# Vile_Boon.net
KiCad netlist of a schematic drawn in EAGLE
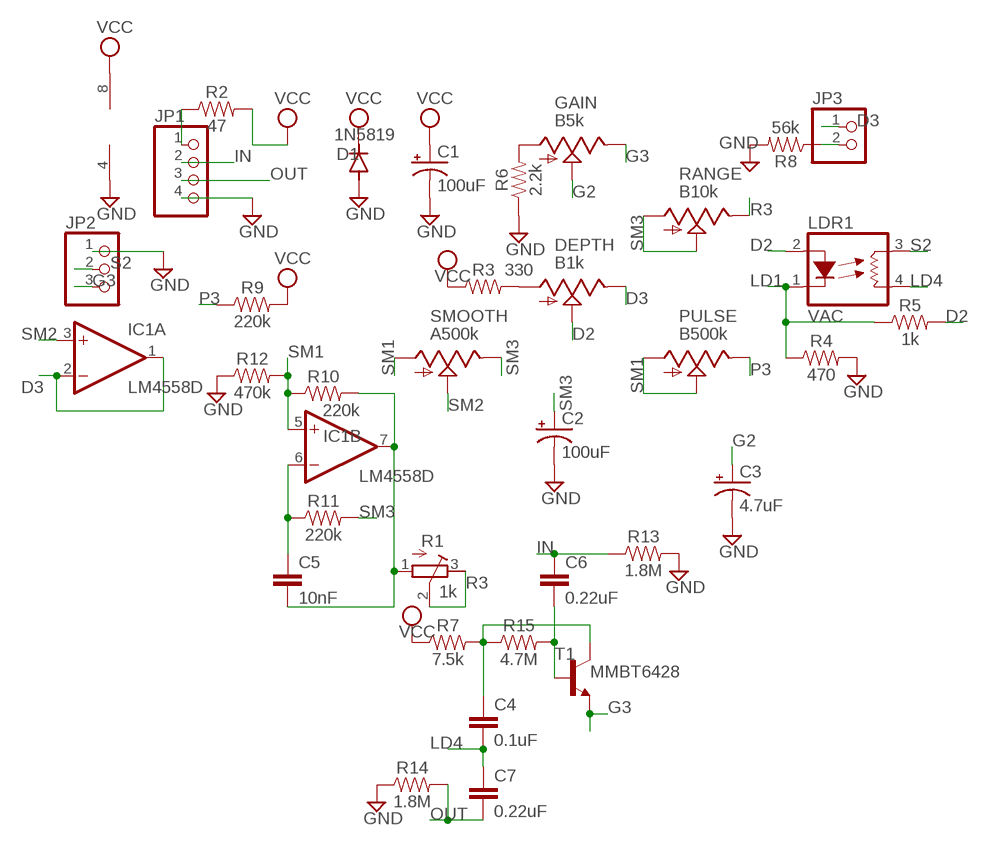
[diagram p0: schematic, sheet 1]

(export (version "E")
  (design (tool "Eeschema 10.0.6"))
  (components
    (comp (ref "C1")
      (value "100uF")
      (footprint "eagle-import:PAN_B_SMD+THRU")
      (libsource (lib "eagle-import") (part "CAP_SMD+THRUPAN_B"))
    )
    (comp (ref "C2")
      (value "100uF")
      (footprint "eagle-import:PAN_B_SMD+THRU")
      (libsource (lib "eagle-import") (part "CAP_SMD+THRUPAN_B"))
    )
    (comp (ref "C3")
      (value "4.7uF")
      (footprint "eagle-import:PAN_B_SMD+THRU")
      (libsource (lib "eagle-import") (part "CAP_SMD+THRUPAN_B"))
    )
    (comp (ref "C4")
      (value "0.1uF")
      (footprint "eagle-import:0603")
      (libsource (lib "eagle-import") (part "0.1UF-0603-25V-(+80/-20%)"))
    )
    (comp (ref "C5")
      (value "10nF")
      (footprint "eagle-import:0603")
      (libsource (lib "eagle-import") (part "10NF-0603-50V-10%"))
    )
    (comp (ref "C6")
      (value "0.22uF")
      (footprint "eagle-import:0603")
      (libsource (lib "eagle-import") (part "0.22UF-0603-25V-10%"))
    )
    (comp (ref "C7")
      (value "0.22uF")
      (footprint "eagle-import:0603")
      (libsource (lib "eagle-import") (part "0.22UF-0603-25V-10%"))
    )
    (comp (ref "D1")
      (value "1N5819")
      (footprint "eagle-import:SOD123")
      (libsource (lib "eagle-import") (part "DIODE-SOD123"))
    )
    (comp (ref "DEPTH")
      (value "B1k")
      (footprint "eagle-import:9MM_SNAP-IN_POT")
      (libsource (lib "eagle-import") (part "9MM_SNAP-IN_POT_"))
    )
    (comp (ref "GAIN")
      (value "B5k")
      (footprint "eagle-import:9MM_SNAP-IN_POT")
      (libsource (lib "eagle-import") (part "9MM_SNAP-IN_POT_"))
    )
    (comp (ref "IC1")
      (value "LM4558D")
      (footprint "eagle-import:SO08")
      (libsource (lib "eagle-import") (part "4558DLM"))
    )
    (comp (ref "JP1")
      (value "PINHD-1X4")
      (footprint "eagle-import:1X04")
      (libsource (lib "eagle-import") (part "PINHD-1X4"))
    )
    (comp (ref "JP2")
      (value "PINHD-1X3")
      (footprint "eagle-import:1X03")
      (libsource (lib "eagle-import") (part "PINHD-1X3"))
    )
    (comp (ref "JP3")
      (value "PINHD-1X2")
      (footprint "eagle-import:1X02")
      (libsource (lib "eagle-import") (part "PINHD-1X2"))
    )
    (comp (ref "LDR1")
      (value "VAC")
      (footprint "eagle-import:VACTROL_4PIN_VTL5C")
      (libsource (lib "eagle-import") (part "VACTROL_4PIN"))
    )
    (comp (ref "PULSE")
      (value "B500k")
      (footprint "eagle-import:9MM_SNAP-IN_POT")
      (libsource (lib "eagle-import") (part "9MM_SNAP-IN_POT_"))
    )
    (comp (ref "R1")
      (value "1k")
      (footprint "eagle-import:RTRIM3296W")
      (libsource (lib "eagle-import") (part "R-TRIMM3296W"))
    )
    (comp (ref "R2")
      (value "47")
      (footprint "eagle-import:0603")
      (libsource (lib "eagle-import") (part "47KOHM-0603-1/10W-1%"))
    )
    (comp (ref "R3")
      (value "330")
      (footprint "eagle-import:0603")
      (libsource (lib "eagle-import") (part "47KOHM-0603-1/10W-1%"))
    )
    (comp (ref "R4")
      (value "470")
      (footprint "eagle-import:0603")
      (libsource (lib "eagle-import") (part "47KOHM-0603-1/10W-1%"))
    )
    (comp (ref "R5")
      (value "1k")
      (footprint "eagle-import:0603")
      (libsource (lib "eagle-import") (part "1KOHM-0603-1/10W-1%"))
    )
    (comp (ref "R6")
      (value "2.2k")
      (footprint "eagle-import:0603")
      (libsource (lib "eagle-import") (part "2.2KOHM-0603-1/10W-1%"))
    )
    (comp (ref "R7")
      (value "7.5k")
      (footprint "eagle-import:0603")
      (libsource (lib "eagle-import") (part "6.8KOHM-0603-1/10W-1%"))
    )
    (comp (ref "R8")
      (value "56k")
      (footprint "eagle-import:0603")
      (libsource (lib "eagle-import") (part "47KOHM-0603-1/10W-1%"))
    )
    (comp (ref "R9")
      (value "220k")
      (footprint "eagle-import:0603")
      (libsource (lib "eagle-import") (part "220KOHM-0603-1/10W-1%"))
    )
    (comp (ref "R10")
      (value "220k")
      (footprint "eagle-import:0603")
      (libsource (lib "eagle-import") (part "220KOHM-0603-1/10W-1%"))
    )
    (comp (ref "R11")
      (value "220k")
      (footprint "eagle-import:0603")
      (libsource (lib "eagle-import") (part "220KOHM-0603-1/10W-1%"))
    )
    (comp (ref "R12")
      (value "470k")
      (footprint "eagle-import:0603")
      (libsource (lib "eagle-import") (part "470OHM-0603-1/10W-1%"))
    )
    (comp (ref "R13")
      (value "1.8M")
      (footprint "eagle-import:0603")
      (libsource (lib "eagle-import") (part "1MOHM-0603-1/4W-5%"))
    )
    (comp (ref "R14")
      (value "1.8M")
      (footprint "eagle-import:0603")
      (libsource (lib "eagle-import") (part "1MOHM-0603-1/4W-5%"))
    )
    (comp (ref "R15")
      (value "4.7M")
      (footprint "eagle-import:0603")
      (libsource (lib "eagle-import") (part "4.7KOHM-0603-1/10W-1%"))
    )
    (comp (ref "RANGE")
      (value "B10k")
      (footprint "eagle-import:9MM_SNAP-IN_POT")
      (libsource (lib "eagle-import") (part "9MM_SNAP-IN_POT_"))
    )
    (comp (ref "SMOOTH")
      (value "A500k")
      (footprint "eagle-import:9MM_SNAP-IN_POT")
      (libsource (lib "eagle-import") (part "9MM_SNAP-IN_POT_"))
    )
    (comp (ref "T1")
      (value "MMBT6428")
      (footprint "eagle-import:SOT23-BEC")
      (libsource (lib "eagle-import") (part "-NPN-SOT23-BECBFS17"))
    )
  )
  (nets
    (net (code "1") (name "/D2") (class "Default")
      (node (ref "DEPTH") (pin "2") (pinfunction "S_2") (pintype "passive"))
      (node (ref "LDR1") (pin "2") (pinfunction "LED+_2") (pintype "passive"))
      (node (ref "R5") (pin "2") (pinfunction "2_2") (pintype "passive"))
    )
    (net (code "2") (name "/D3") (class "Default")
      (node (ref "DEPTH") (pin "3") (pinfunction "E_3") (pintype "passive"))
      (node (ref "IC1") (pin "1") (pinfunction "OUT_1") (pintype "output"))
      (node (ref "IC1") (pin "2") (pinfunction "-IN_2") (pintype "input"))
      (node (ref "JP3") (pin "1") (pinfunction "1_1") (pintype "passive"))
    )
    (net (code "3") (name "/G2") (class "Default")
      (node (ref "C3") (pin "+") (pinfunction "+_+") (pintype "passive"))
      (node (ref "C3") (pin "++") (pinfunction "+_++") (pintype "passive"))
      (node (ref "GAIN") (pin "2") (pinfunction "S_2") (pintype "passive"))
    )
    (net (code "4") (name "/G3") (class "Default")
      (node (ref "GAIN") (pin "3") (pinfunction "E_3") (pintype "passive"))
      (node (ref "JP2") (pin "3") (pinfunction "3_3") (pintype "passive"))
      (node (ref "T1") (pin "E") (pinfunction "E_E") (pintype "passive"))
    )
    (net (code "5") (name "/IN") (class "Default")
      (node (ref "C6") (pin "1") (pinfunction "1_1") (pintype "passive"))
      (node (ref "JP1") (pin "2") (pinfunction "2_2") (pintype "passive"))
      (node (ref "R13") (pin "1") (pinfunction "1_1") (pintype "passive"))
    )
    (net (code "6") (name "/LD1") (class "Default")
      (node (ref "LDR1") (pin "1") (pinfunction "LED-_1") (pintype "passive"))
      (node (ref "R4") (pin "1") (pinfunction "1_1") (pintype "passive"))
      (node (ref "R5") (pin "1") (pinfunction "1_1") (pintype "passive"))
    )
    (net (code "7") (name "/LD4") (class "Default")
      (node (ref "C4") (pin "2") (pinfunction "2_2") (pintype "passive"))
      (node (ref "C7") (pin "1") (pinfunction "1_1") (pintype "passive"))
      (node (ref "LDR1") (pin "4") (pinfunction "RES2_4") (pintype "passive"))
    )
    (net (code "8") (name "/OUT") (class "Default")
      (node (ref "C7") (pin "2") (pinfunction "2_2") (pintype "passive"))
      (node (ref "JP1") (pin "3") (pinfunction "3_3") (pintype "passive"))
      (node (ref "R14") (pin "2") (pinfunction "2_2") (pintype "passive"))
    )
    (net (code "9") (name "/P3") (class "Default")
      (node (ref "PULSE") (pin "3") (pinfunction "E_3") (pintype "passive"))
      (node (ref "R9") (pin "1") (pinfunction "1_1") (pintype "passive"))
    )
    (net (code "10") (name "/R3") (class "Default")
      (node (ref "R1") (pin "2") (pinfunction "S_2") (pintype "passive"))
      (node (ref "R1") (pin "3") (pinfunction "E_3") (pintype "passive"))
      (node (ref "RANGE") (pin "3") (pinfunction "E_3") (pintype "passive"))
    )
    (net (code "11") (name "/S2") (class "Default")
      (node (ref "JP2") (pin "2") (pinfunction "2_2") (pintype "passive"))
      (node (ref "LDR1") (pin "3") (pinfunction "RES1_3") (pintype "passive"))
    )
    (net (code "12") (name "/SM1") (class "Default")
      (node (ref "IC1") (pin "5") (pinfunction "+IN_5") (pintype "input"))
      (node (ref "PULSE") (pin "1") (pinfunction "A_1") (pintype "passive"))
      (node (ref "PULSE") (pin "2") (pinfunction "S_2") (pintype "passive"))
      (node (ref "R10") (pin "1") (pinfunction "1_1") (pintype "passive"))
      (node (ref "R12") (pin "2") (pinfunction "2_2") (pintype "passive"))
      (node (ref "SMOOTH") (pin "1") (pinfunction "A_1") (pintype "passive"))
    )
    (net (code "13") (name "/SM2") (class "Default")
      (node (ref "IC1") (pin "3") (pinfunction "+IN_3") (pintype "input"))
      (node (ref "SMOOTH") (pin "2") (pinfunction "S_2") (pintype "passive"))
    )
    (net (code "14") (name "/SM3") (class "Default")
      (node (ref "C2") (pin "+") (pinfunction "+_+") (pintype "passive"))
      (node (ref "C2") (pin "++") (pinfunction "+_++") (pintype "passive"))
      (node (ref "R11") (pin "2") (pinfunction "2_2") (pintype "passive"))
      (node (ref "RANGE") (pin "1") (pinfunction "A_1") (pintype "passive"))
      (node (ref "RANGE") (pin "2") (pinfunction "S_2") (pintype "passive"))
      (node (ref "SMOOTH") (pin "3") (pinfunction "E_3") (pintype "passive"))
    )
    (net (code "15") (name "GND") (class "Default")
      (node (ref "C1") (pin "-") (pinfunction "-_-") (pintype "passive"))
      (node (ref "C1") (pin "--") (pinfunction "-_--") (pintype "passive"))
      (node (ref "C2") (pin "-") (pinfunction "-_-") (pintype "passive"))
      (node (ref "C2") (pin "--") (pinfunction "-_--") (pintype "passive"))
      (node (ref "C3") (pin "-") (pinfunction "-_-") (pintype "passive"))
      (node (ref "C3") (pin "--") (pinfunction "-_--") (pintype "passive"))
      (node (ref "D1") (pin "A") (pinfunction "A_A") (pintype "passive"))
      (node (ref "IC1") (pin "4") (pinfunction "V-_4") (pintype "power_in"))
      (node (ref "JP1") (pin "4") (pinfunction "4_4") (pintype "passive"))
      (node (ref "JP2") (pin "1") (pinfunction "1_1") (pintype "passive"))
      (node (ref "R12") (pin "1") (pinfunction "1_1") (pintype "passive"))
      (node (ref "R13") (pin "2") (pinfunction "2_2") (pintype "passive"))
      (node (ref "R14") (pin "1") (pinfunction "1_1") (pintype "passive"))
      (node (ref "R4") (pin "2") (pinfunction "2_2") (pintype "passive"))
      (node (ref "R6") (pin "1") (pinfunction "1_1") (pintype "passive"))
      (node (ref "R8") (pin "2") (pinfunction "2_2") (pintype "passive"))
    )
    (net (code "16") (name "Net-(C4-Pad1)") (class "Default")
      (node (ref "C4") (pin "1") (pinfunction "1_1") (pintype "passive"))
      (node (ref "R15") (pin "1") (pinfunction "1_1") (pintype "passive"))
      (node (ref "R7") (pin "2") (pinfunction "2_2") (pintype "passive"))
      (node (ref "T1") (pin "C") (pinfunction "C_C") (pintype "passive"))
    )
    (net (code "17") (name "Net-(C6-Pad2)") (class "Default")
      (node (ref "C6") (pin "2") (pinfunction "2_2") (pintype "passive"))
      (node (ref "R15") (pin "2") (pinfunction "2_2") (pintype "passive"))
      (node (ref "T1") (pin "B") (pinfunction "B_B") (pintype "passive"))
    )
    (net (code "18") (name "Net-(DEPTH-A)") (class "Default")
      (node (ref "DEPTH") (pin "1") (pinfunction "A_1") (pintype "passive"))
      (node (ref "R3") (pin "2") (pinfunction "2_2") (pintype "passive"))
    )
    (net (code "19") (name "Net-(GAIN-A)") (class "Default")
      (node (ref "GAIN") (pin "1") (pinfunction "A_1") (pintype "passive"))
      (node (ref "R6") (pin "2") (pinfunction "2_2") (pintype "passive"))
    )
    (net (code "20") (name "Net-(IC1B--IN)") (class "Default")
      (node (ref "C5") (pin "1") (pinfunction "1_1") (pintype "passive"))
      (node (ref "IC1") (pin "6") (pinfunction "-IN_6") (pintype "input"))
      (node (ref "R11") (pin "1") (pinfunction "1_1") (pintype "passive"))
    )
    (net (code "21") (name "Net-(IC1B-OUT)") (class "Default")
      (node (ref "C5") (pin "2") (pinfunction "2_2") (pintype "passive"))
      (node (ref "IC1") (pin "7") (pinfunction "OUT_7") (pintype "output"))
      (node (ref "R1") (pin "1") (pinfunction "A_1") (pintype "passive"))
      (node (ref "R10") (pin "2") (pinfunction "2_2") (pintype "passive"))
    )
    (net (code "22") (name "Net-(JP1-Pad1)") (class "Default")
      (node (ref "JP1") (pin "1") (pinfunction "1_1") (pintype "passive"))
      (node (ref "R2") (pin "1") (pinfunction "1_1") (pintype "passive"))
    )
    (net (code "23") (name "Net-(JP3-Pad2)") (class "Default")
      (node (ref "JP3") (pin "2") (pinfunction "2_2") (pintype "passive"))
      (node (ref "R8") (pin "1") (pinfunction "1_1") (pintype "passive"))
    )
    (net (code "24") (name "VCC") (class "Default")
      (node (ref "C1") (pin "+") (pinfunction "+_+") (pintype "passive"))
      (node (ref "C1") (pin "++") (pinfunction "+_++") (pintype "passive"))
      (node (ref "D1") (pin "C") (pinfunction "C_C") (pintype "passive"))
      (node (ref "IC1") (pin "8") (pinfunction "V+_8") (pintype "power_in"))
      (node (ref "R2") (pin "2") (pinfunction "2_2") (pintype "passive"))
      (node (ref "R3") (pin "1") (pinfunction "1_1") (pintype "passive"))
      (node (ref "R7") (pin "1") (pinfunction "1_1") (pintype "passive"))
      (node (ref "R9") (pin "2") (pinfunction "2_2") (pintype "passive"))
    )
  )
)
